# bm1397.net
KiCad netlist of a schematic drawn in EAGLE
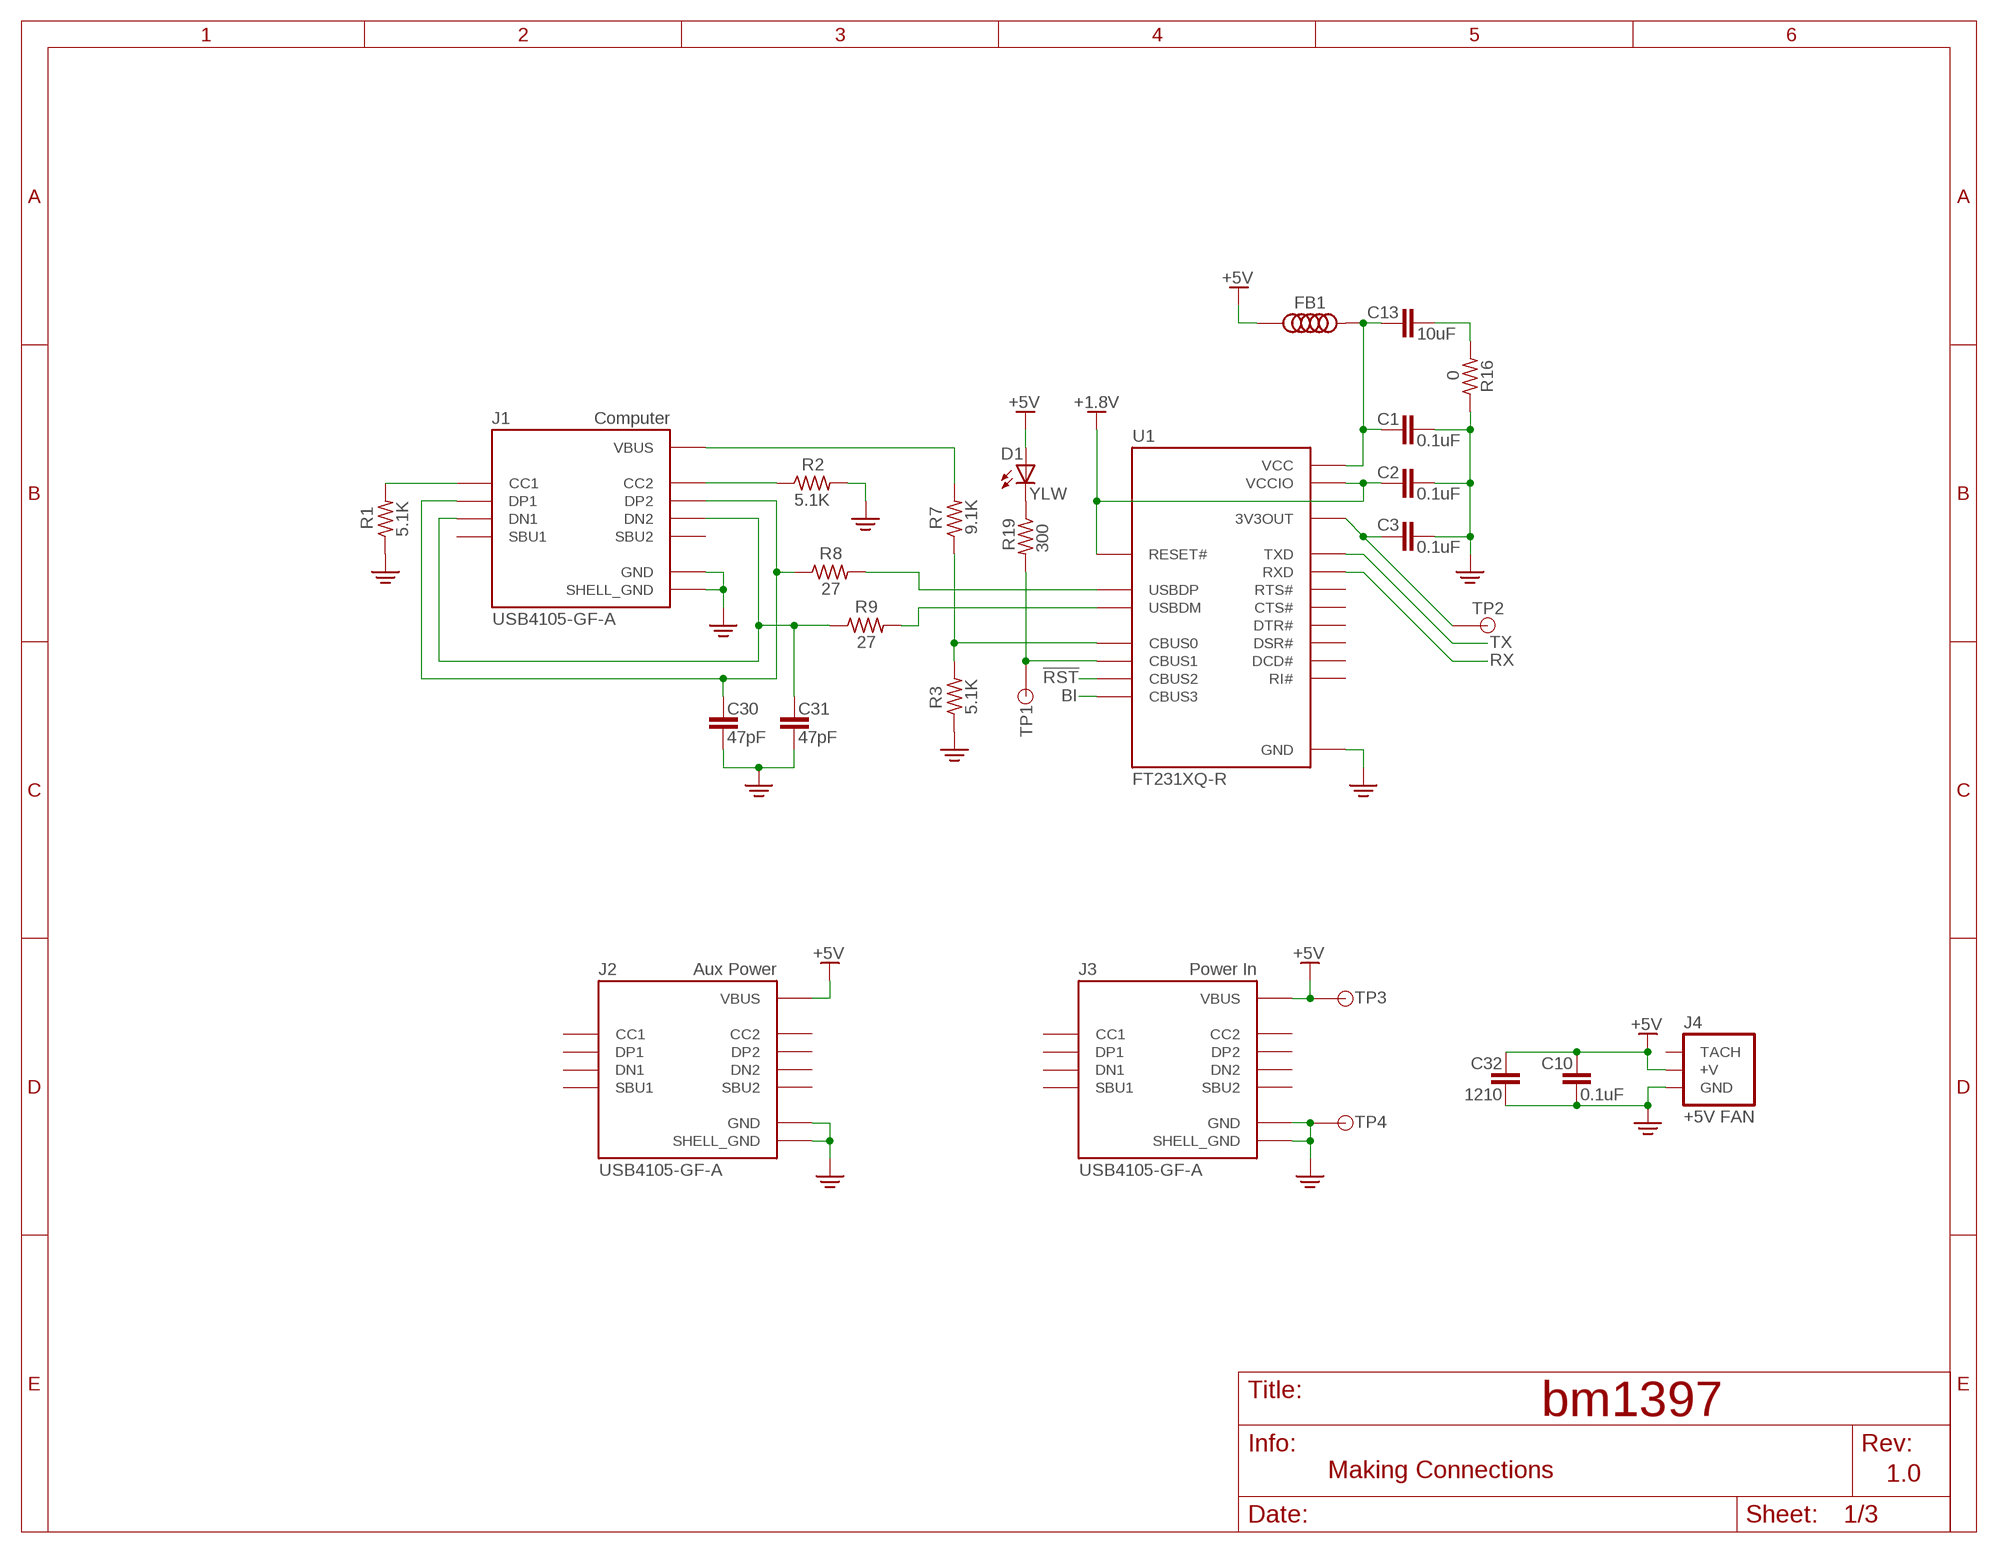
[diagram p0: schematic, sheet 1]
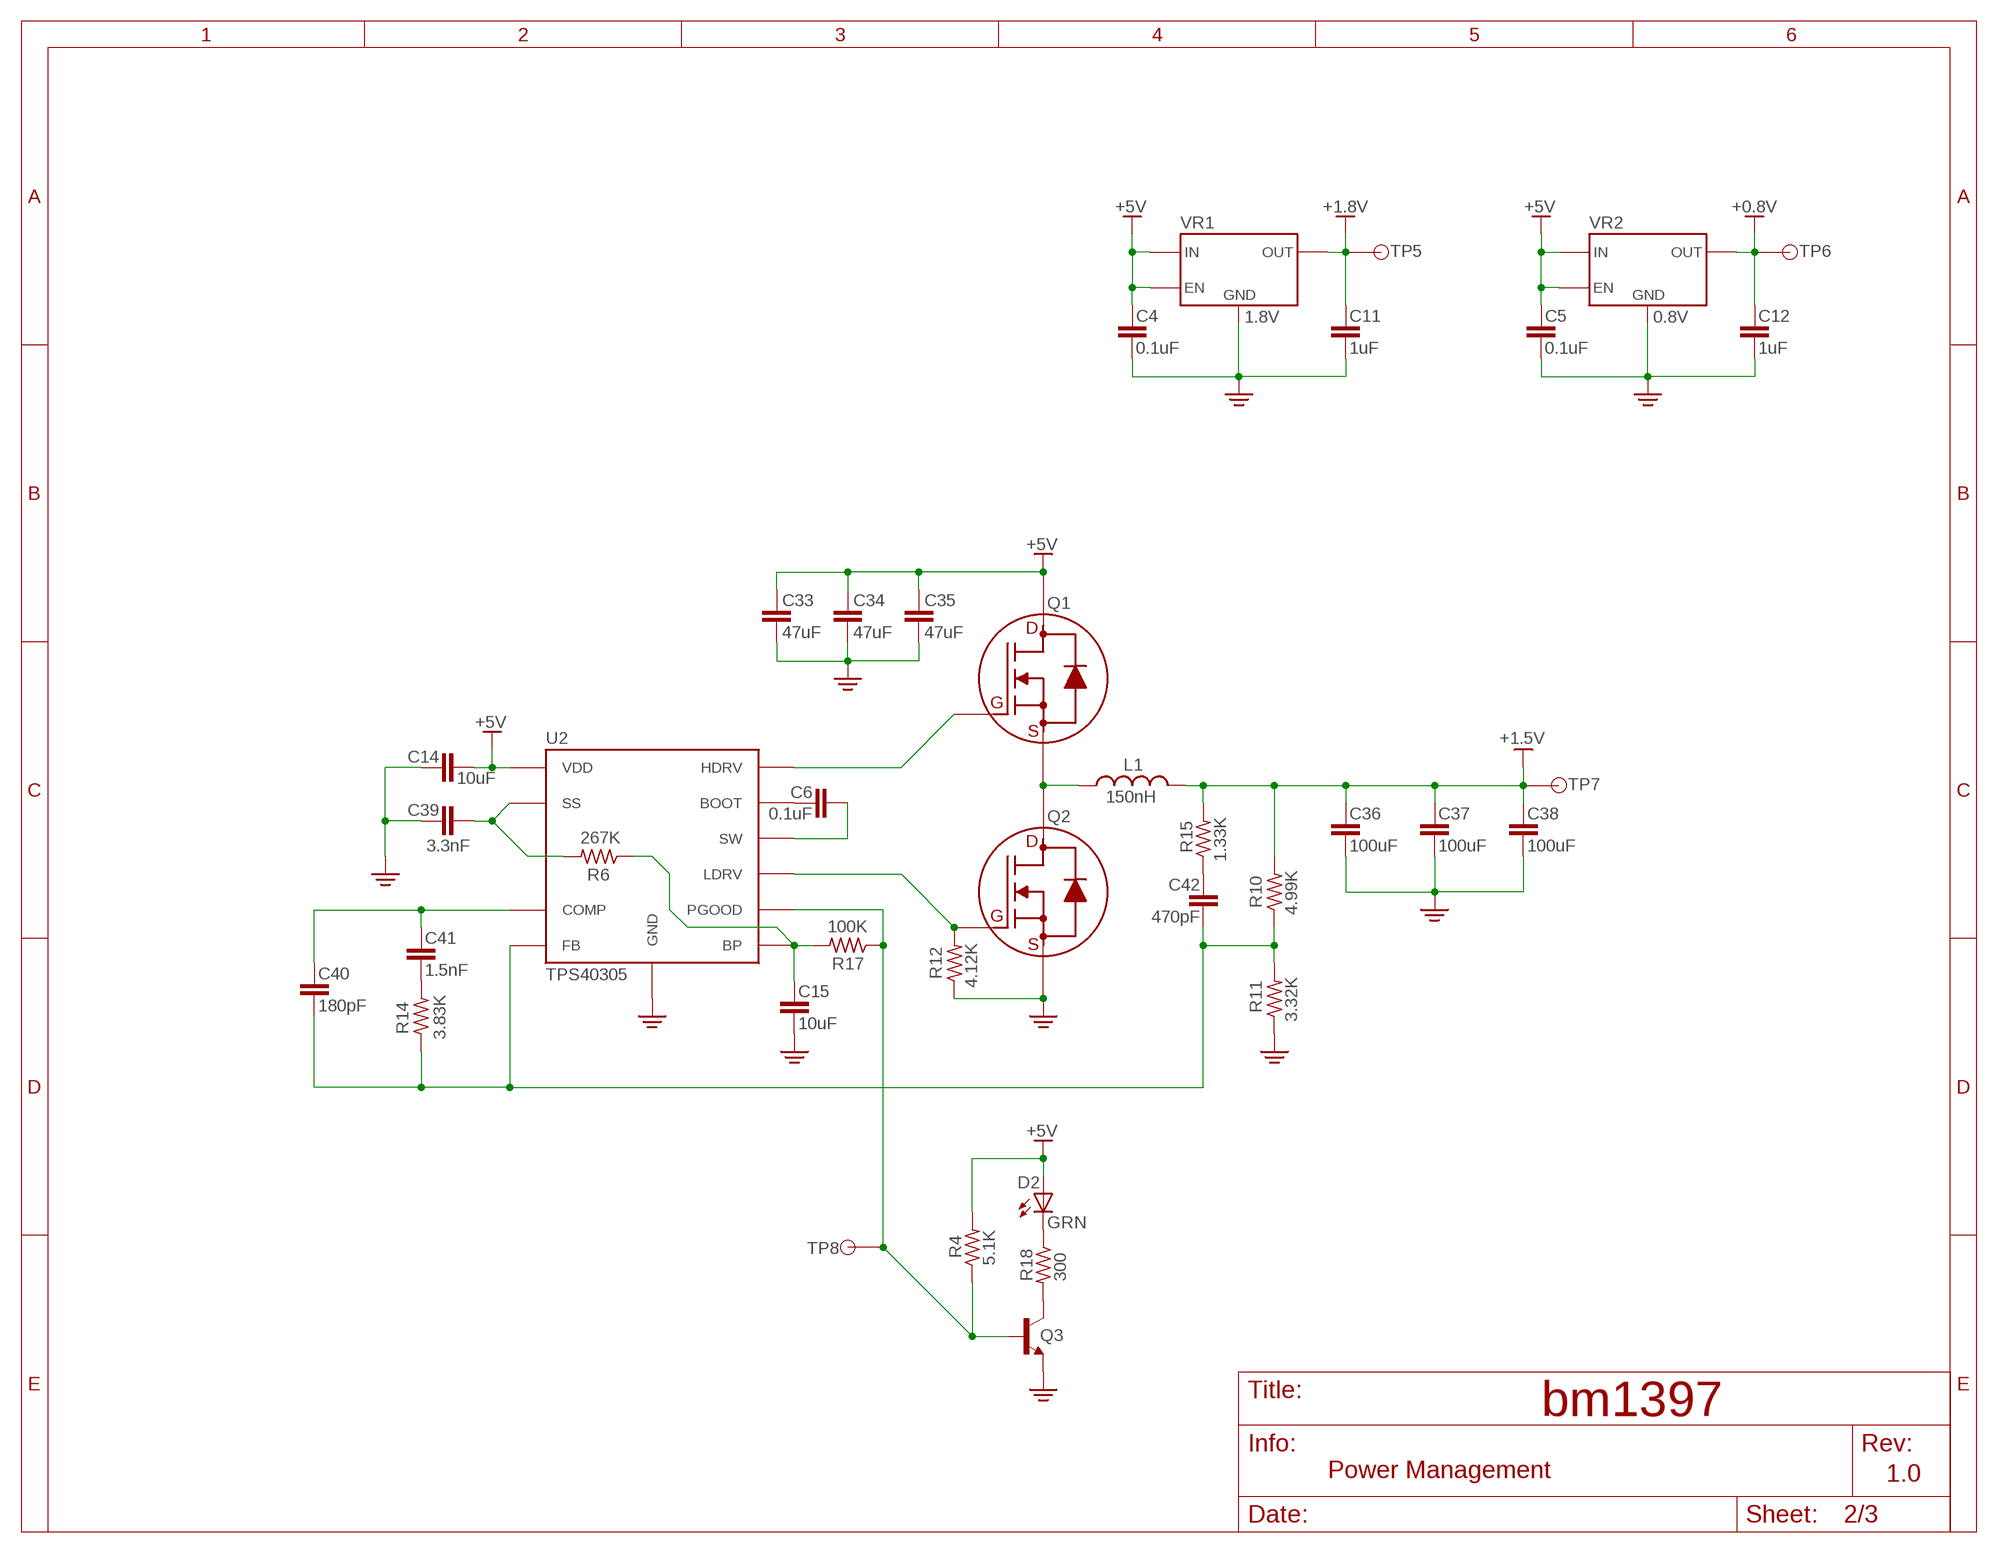
[diagram p1: schematic, sheet 2]
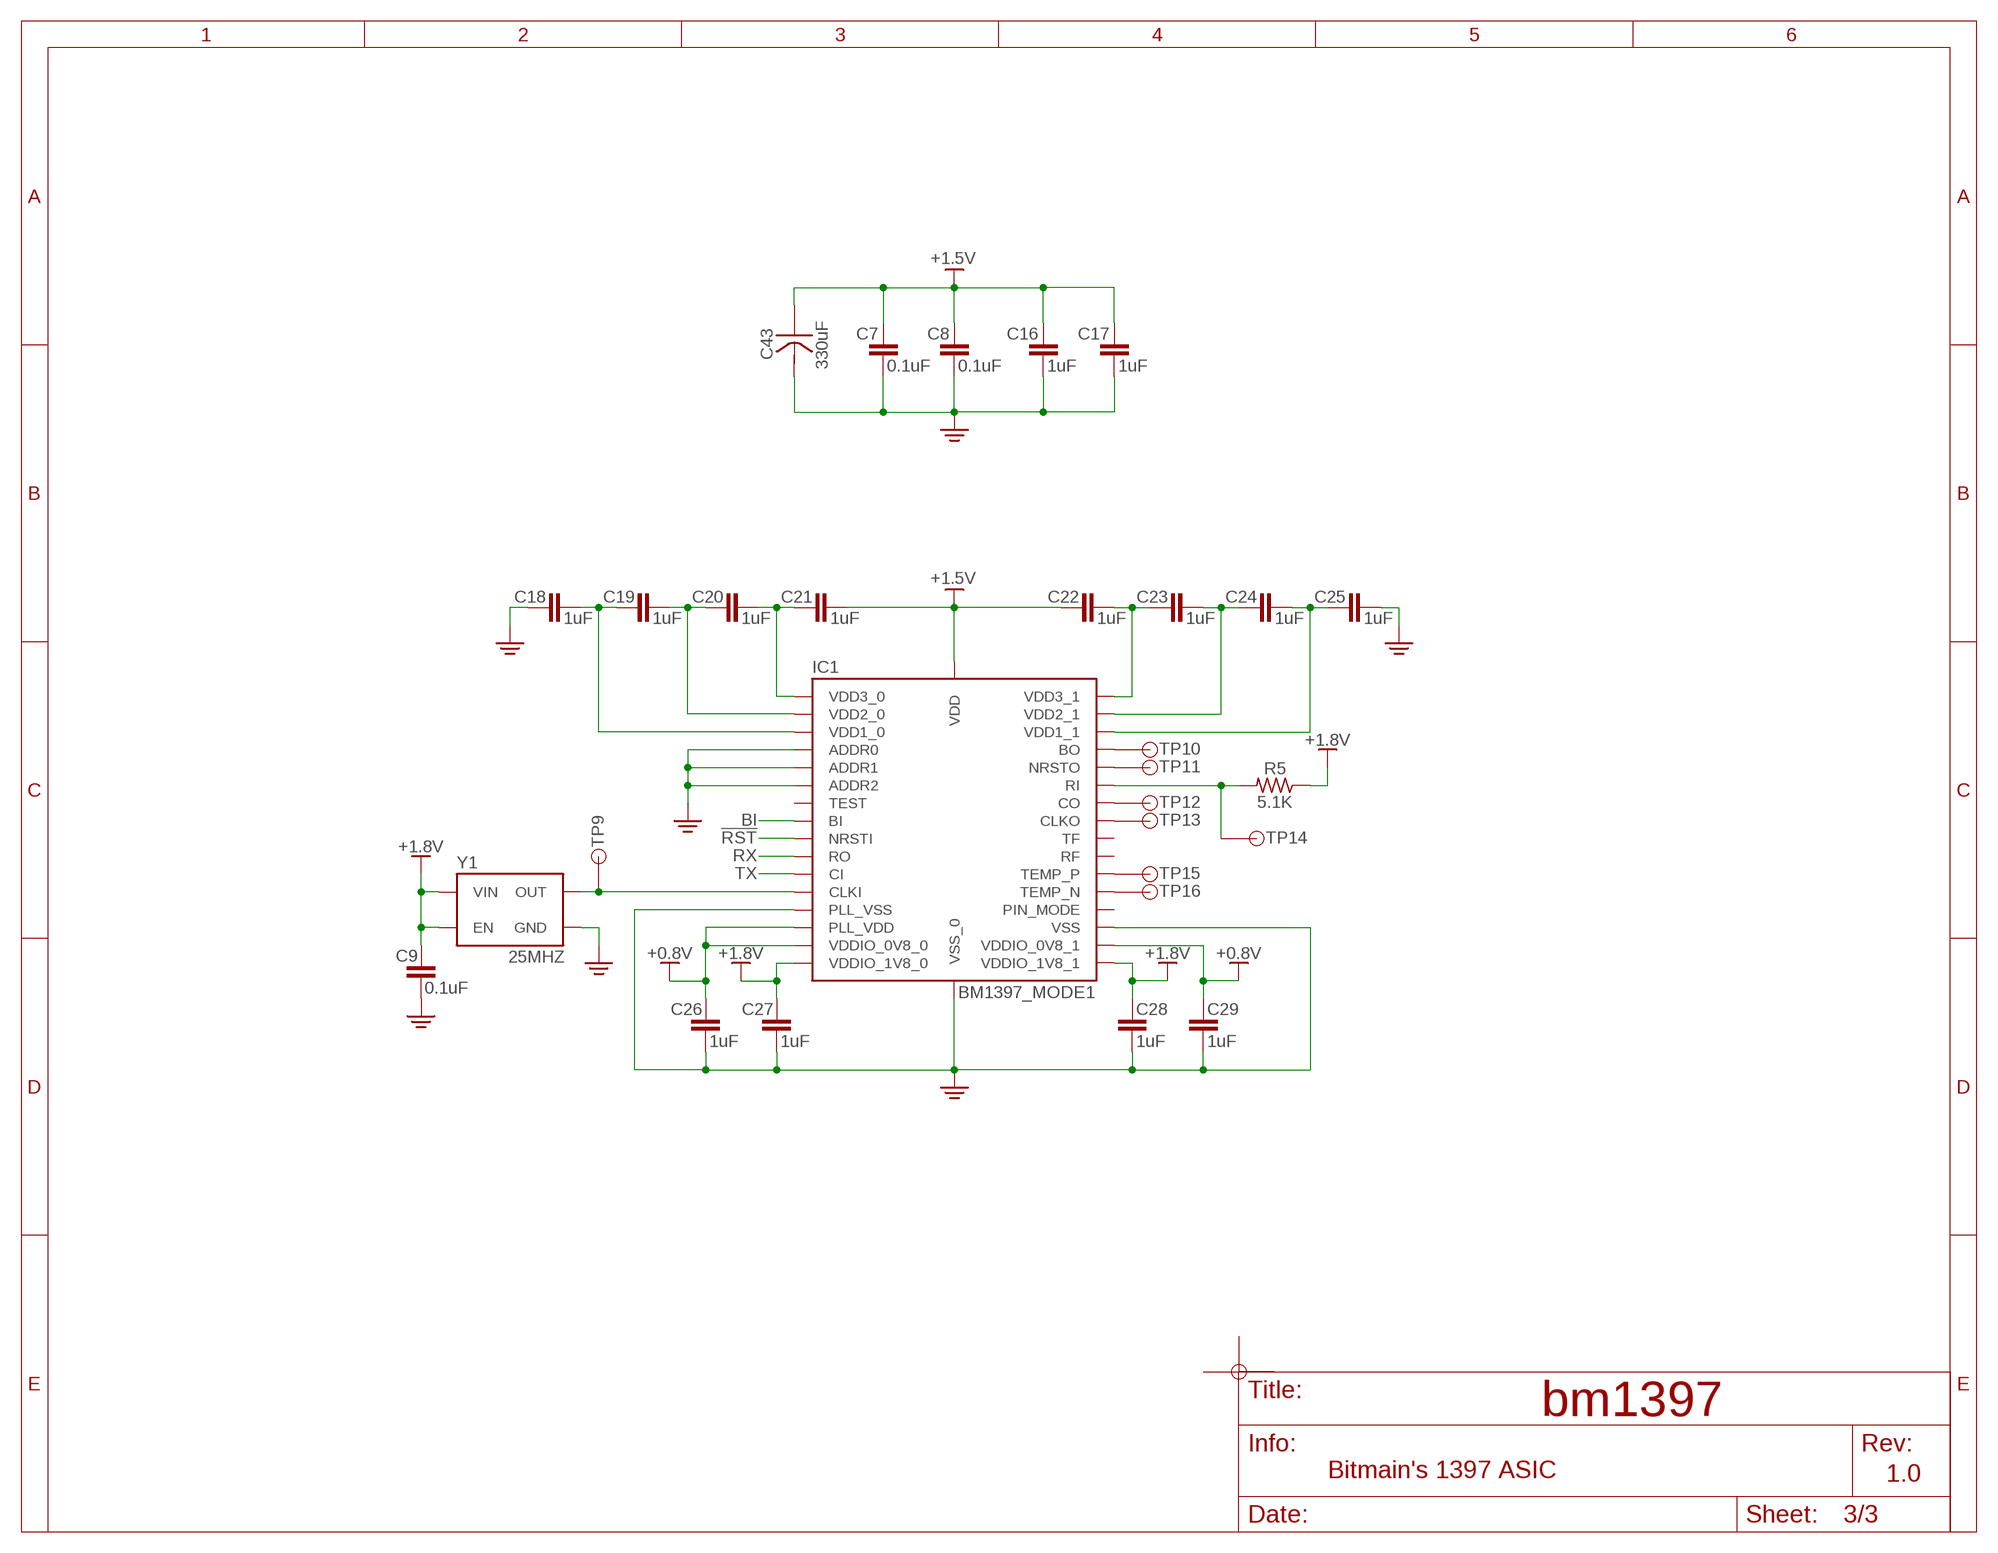
[diagram p2: schematic, sheet 3]

(export (version "E")
  (design (tool "Eeschema 10.0.6"))
  (components
    (comp (ref "BOTFIDUCIAL1")
      (value "TESTPOINT")
      (footprint "eagle-import:0.035")
      (libsource (lib "eagle-import") (part "TESTPOINT"))
    )
    (comp (ref "BOTFIDUCIAL2")
      (value "TESTPOINT")
      (footprint "eagle-import:0.035")
      (libsource (lib "eagle-import") (part "TESTPOINT"))
    )
    (comp (ref "BOTFIDUCIAL3")
      (value "TESTPOINT")
      (footprint "eagle-import:0.035")
      (libsource (lib "eagle-import") (part "TESTPOINT"))
    )
    (comp (ref "C7")
      (value "0.1uF")
      (footprint "eagle-import:C0402")
      (libsource (lib "eagle-import") (part "NPOL_CAPACITORC0402"))
    )
    (comp (ref "C8")
      (value "0.1uF")
      (footprint "eagle-import:C0402")
      (libsource (lib "eagle-import") (part "NPOL_CAPACITORC0402"))
    )
    (comp (ref "C9")
      (value "0.1uF")
      (footprint "eagle-import:C0402")
      (libsource (lib "eagle-import") (part "NPOL_CAPACITORC0402"))
    )
    (comp (ref "C16")
      (value "1uF")
      (footprint "eagle-import:C0603")
      (libsource (lib "eagle-import") (part "NPOL_CAPACITORC0603"))
    )
    (comp (ref "C17")
      (value "1uF")
      (footprint "eagle-import:C0603")
      (libsource (lib "eagle-import") (part "NPOL_CAPACITORC0603"))
    )
    (comp (ref "C18")
      (value "1uF")
      (footprint "eagle-import:C0603")
      (libsource (lib "eagle-import") (part "NPOL_CAPACITORC0603"))
    )
    (comp (ref "C19")
      (value "1uF")
      (footprint "eagle-import:C0603")
      (libsource (lib "eagle-import") (part "NPOL_CAPACITORC0603"))
    )
    (comp (ref "C20")
      (value "1uF")
      (footprint "eagle-import:C0603")
      (libsource (lib "eagle-import") (part "NPOL_CAPACITORC0603"))
    )
    (comp (ref "C21")
      (value "1uF")
      (footprint "eagle-import:C0603")
      (libsource (lib "eagle-import") (part "NPOL_CAPACITORC0603"))
    )
    (comp (ref "C22")
      (value "1uF")
      (footprint "eagle-import:C0603")
      (libsource (lib "eagle-import") (part "NPOL_CAPACITORC0603"))
    )
    (comp (ref "C23")
      (value "1uF")
      (footprint "eagle-import:C0603")
      (libsource (lib "eagle-import") (part "NPOL_CAPACITORC0603"))
    )
    (comp (ref "C24")
      (value "1uF")
      (footprint "eagle-import:C0603")
      (libsource (lib "eagle-import") (part "NPOL_CAPACITORC0603"))
    )
    (comp (ref "C25")
      (value "1uF")
      (footprint "eagle-import:C0603")
      (libsource (lib "eagle-import") (part "NPOL_CAPACITORC0603"))
    )
    (comp (ref "C26")
      (value "1uF")
      (footprint "eagle-import:C0603")
      (libsource (lib "eagle-import") (part "NPOL_CAPACITORC0603"))
    )
    (comp (ref "C27")
      (value "1uF")
      (footprint "eagle-import:C0603")
      (libsource (lib "eagle-import") (part "NPOL_CAPACITORC0603"))
    )
    (comp (ref "C28")
      (value "1uF")
      (footprint "eagle-import:C0603")
      (libsource (lib "eagle-import") (part "NPOL_CAPACITORC0603"))
    )
    (comp (ref "C29")
      (value "1uF")
      (footprint "eagle-import:C0603")
      (libsource (lib "eagle-import") (part "NPOL_CAPACITORC0603"))
    )
    (comp (ref "C43")
      (value "330uF")
      (footprint "eagle-import:TANT_3.5MMX2.8MM")
      (libsource (lib "eagle-import") (part "POL_CAPACITORTANT_3.5MMX2.8MM"))
    )
    (comp (ref "IC1")
      (value "BM1397_MODE1")
      (footprint "eagle-import:BM1397")
      (libsource (lib "eagle-import") (part "BM1397_MODE1"))
    )
    (comp (ref "R5")
      (value "5.1K")
      (footprint "eagle-import:R0402")
      (libsource (lib "eagle-import") (part "RESISTORR0402"))
    )
    (comp (ref "TOPFIDUCIAL1")
      (value "TESTPOINT")
      (footprint "eagle-import:0.035")
      (libsource (lib "eagle-import") (part "TESTPOINT"))
    )
    (comp (ref "TOPFIDUCIAL2")
      (value "TESTPOINT")
      (footprint "eagle-import:0.035")
      (libsource (lib "eagle-import") (part "TESTPOINT"))
    )
    (comp (ref "TOPFIDUCIAL3")
      (value "TESTPOINT")
      (footprint "eagle-import:0.035")
      (libsource (lib "eagle-import") (part "TESTPOINT"))
    )
    (comp (ref "TP9")
      (value "TESTPOINT")
      (footprint "eagle-import:0.035")
      (libsource (lib "eagle-import") (part "TESTPOINT"))
    )
    (comp (ref "TP10")
      (value "TESTPOINT")
      (footprint "eagle-import:0.035")
      (libsource (lib "eagle-import") (part "TESTPOINT"))
    )
    (comp (ref "TP11")
      (value "TESTPOINT")
      (footprint "eagle-import:0.035")
      (libsource (lib "eagle-import") (part "TESTPOINT"))
    )
    (comp (ref "TP12")
      (value "TESTPOINT")
      (footprint "eagle-import:0.035")
      (libsource (lib "eagle-import") (part "TESTPOINT"))
    )
    (comp (ref "TP13")
      (value "TESTPOINT")
      (footprint "eagle-import:0.035")
      (libsource (lib "eagle-import") (part "TESTPOINT"))
    )
    (comp (ref "TP14")
      (value "TESTPOINT")
      (footprint "eagle-import:0.035")
      (libsource (lib "eagle-import") (part "TESTPOINT"))
    )
    (comp (ref "TP15")
      (value "TESTPOINT")
      (footprint "eagle-import:0.035")
      (libsource (lib "eagle-import") (part "TESTPOINT"))
    )
    (comp (ref "TP16")
      (value "TESTPOINT")
      (footprint "eagle-import:0.035")
      (libsource (lib "eagle-import") (part "TESTPOINT"))
    )
    (comp (ref "Y1")
      (value "25MHZ")
      (footprint "eagle-import:JO32_3.20MMX2.50MM")
      (libsource (lib "eagle-import") (part "JO32_OSCILLATOR"))
    )
    (comp (ref "C1")
      (value "0.1uF")
      (footprint "eagle-import:C0402")
      (libsource (lib "eagle-import") (part "NPOL_CAPACITORC0402"))
    )
    (comp (ref "C2")
      (value "0.1uF")
      (footprint "eagle-import:C0402")
      (libsource (lib "eagle-import") (part "NPOL_CAPACITORC0402"))
    )
    (comp (ref "C3")
      (value "0.1uF")
      (footprint "eagle-import:C0402")
      (libsource (lib "eagle-import") (part "NPOL_CAPACITORC0402"))
    )
    (comp (ref "C10")
      (value "0.1uF")
      (footprint "eagle-import:C0402")
      (libsource (lib "eagle-import") (part "NPOL_CAPACITORC0402"))
    )
    (comp (ref "C13")
      (value "10uF")
      (footprint "eagle-import:C0805")
      (libsource (lib "eagle-import") (part "NPOL_CAPACITORC0805"))
    )
    (comp (ref "C30")
      (value "47pF")
      (footprint "eagle-import:C0402")
      (libsource (lib "eagle-import") (part "NPOL_CAPACITORC0402"))
    )
    (comp (ref "C31")
      (value "47pF")
      (footprint "eagle-import:C0402")
      (libsource (lib "eagle-import") (part "NPOL_CAPACITORC0402"))
    )
    (comp (ref "C32")
      (value "1210")
      (footprint "eagle-import:C1210")
      (libsource (lib "eagle-import") (part "NPOL_CAPACITORC1210"))
    )
    (comp (ref "D1")
      (value "YLW")
      (footprint "eagle-import:0805_SD_MNT")
      (libsource (lib "eagle-import") (part "LED"))
    )
    (comp (ref "FB1")
      (value "FERRITE_BEADF0402")
      (footprint "eagle-import:F0402")
      (libsource (lib "eagle-import") (part "FERRITE_BEADF0402"))
    )
    (comp (ref "J1")
      (value "USB4105-GF-A")
      (footprint "eagle-import:GCT_USB4105-GF-A")
      (fields (field (name "MF") "GCT"))
      (libsource (lib "eagle-import") (part "USB4105-GF-A"))
    )
    (comp (ref "J2")
      (value "USB4105-GF-A")
      (footprint "eagle-import:GCT_USB4105-GF-A")
      (fields (field (name "MF") "GCT"))
      (libsource (lib "eagle-import") (part "USB4105-GF-A"))
    )
    (comp (ref "J3")
      (value "USB4105-GF-A")
      (footprint "eagle-import:GCT_USB4105-GF-A")
      (fields (field (name "MF") "GCT"))
      (libsource (lib "eagle-import") (part "USB4105-GF-A"))
    )
    (comp (ref "J4")
      (value "+5V FAN")
      (footprint "eagle-import:3PIN_LOCK_HEADER")
      (libsource (lib "eagle-import") (part "3PIN_FAN3PIN_FAN"))
    )
    (comp (ref "R1")
      (value "5.1K")
      (footprint "eagle-import:R0402")
      (libsource (lib "eagle-import") (part "RESISTORR0402"))
    )
    (comp (ref "R2")
      (value "5.1K")
      (footprint "eagle-import:R0402")
      (libsource (lib "eagle-import") (part "RESISTORR0402"))
    )
    (comp (ref "R3")
      (value "5.1K")
      (footprint "eagle-import:R0402")
      (libsource (lib "eagle-import") (part "RESISTORR0402"))
    )
    (comp (ref "R7")
      (value "9.1K")
      (footprint "eagle-import:R0402")
      (libsource (lib "eagle-import") (part "RESISTORR0402"))
    )
    (comp (ref "R8")
      (value "27")
      (footprint "eagle-import:R0402")
      (libsource (lib "eagle-import") (part "RESISTORR0402"))
    )
    (comp (ref "R9")
      (value "27")
      (footprint "eagle-import:R0402")
      (libsource (lib "eagle-import") (part "RESISTORR0402"))
    )
    (comp (ref "R16")
      (value "0")
      (footprint "eagle-import:R0402")
      (libsource (lib "eagle-import") (part "RESISTORR0402"))
    )
    (comp (ref "R19")
      (value "300")
      (footprint "eagle-import:R0402")
      (libsource (lib "eagle-import") (part "RESISTORR0402"))
    )
    (comp (ref "TP1")
      (value "TESTPOINT")
      (footprint "eagle-import:0.035")
      (libsource (lib "eagle-import") (part "TESTPOINT"))
    )
    (comp (ref "TP2")
      (value "TESTPOINT")
      (footprint "eagle-import:0.035")
      (libsource (lib "eagle-import") (part "TESTPOINT"))
    )
    (comp (ref "TP3")
      (value "TESTPOINT")
      (footprint "eagle-import:0.035")
      (libsource (lib "eagle-import") (part "TESTPOINT"))
    )
    (comp (ref "TP4")
      (value "TESTPOINT")
      (footprint "eagle-import:0.035")
      (libsource (lib "eagle-import") (part "TESTPOINT"))
    )
    (comp (ref "U1")
      (value "FT231XQ-R")
      (footprint "eagle-import:QFN50P400X400X80-21N")
      (fields (field (name "MF") "FTDI, Future"))
      (libsource (lib "eagle-import") (part "FT231XQ-R"))
    )
    (comp (ref "C4")
      (value "0.1uF")
      (footprint "eagle-import:C0402")
      (libsource (lib "eagle-import") (part "NPOL_CAPACITORC0402"))
    )
    (comp (ref "C5")
      (value "0.1uF")
      (footprint "eagle-import:C0402")
      (libsource (lib "eagle-import") (part "NPOL_CAPACITORC0402"))
    )
    (comp (ref "C6")
      (value "0.1uF")
      (footprint "eagle-import:C0402")
      (libsource (lib "eagle-import") (part "NPOL_CAPACITORC0402"))
    )
    (comp (ref "C11")
      (value "1uF")
      (footprint "eagle-import:C0603")
      (libsource (lib "eagle-import") (part "NPOL_CAPACITORC0603"))
    )
    (comp (ref "C12")
      (value "1uF")
      (footprint "eagle-import:C0603")
      (libsource (lib "eagle-import") (part "NPOL_CAPACITORC0603"))
    )
    (comp (ref "C14")
      (value "10uF")
      (footprint "eagle-import:C0805")
      (libsource (lib "eagle-import") (part "NPOL_CAPACITORC0805"))
    )
    (comp (ref "C15")
      (value "10uF")
      (footprint "eagle-import:C0805")
      (libsource (lib "eagle-import") (part "NPOL_CAPACITORC0805"))
    )
    (comp (ref "C33")
      (value "47uF")
      (footprint "eagle-import:C1210")
      (libsource (lib "eagle-import") (part "NPOL_CAPACITORC1210"))
    )
    (comp (ref "C34")
      (value "47uF")
      (footprint "eagle-import:C1210")
      (libsource (lib "eagle-import") (part "NPOL_CAPACITORC1210"))
    )
    (comp (ref "C35")
      (value "47uF")
      (footprint "eagle-import:C1210")
      (libsource (lib "eagle-import") (part "NPOL_CAPACITORC1210"))
    )
    (comp (ref "C36")
      (value "100uF")
      (footprint "eagle-import:C1210")
      (libsource (lib "eagle-import") (part "NPOL_CAPACITORC1210"))
    )
    (comp (ref "C37")
      (value "100uF")
      (footprint "eagle-import:C1210")
      (libsource (lib "eagle-import") (part "NPOL_CAPACITORC1210"))
    )
    (comp (ref "C38")
      (value "100uF")
      (footprint "eagle-import:C1210")
      (libsource (lib "eagle-import") (part "NPOL_CAPACITORC1210"))
    )
    (comp (ref "C39")
      (value "3.3nF")
      (footprint "eagle-import:C0402")
      (libsource (lib "eagle-import") (part "NPOL_CAPACITORC0402"))
    )
    (comp (ref "C40")
      (value "180pF")
      (footprint "eagle-import:C0402")
      (libsource (lib "eagle-import") (part "NPOL_CAPACITORC0402"))
    )
    (comp (ref "C41")
      (value "1.5nF")
      (footprint "eagle-import:C0402")
      (libsource (lib "eagle-import") (part "NPOL_CAPACITORC0402"))
    )
    (comp (ref "C42")
      (value "470pF")
      (footprint "eagle-import:C0402")
      (libsource (lib "eagle-import") (part "NPOL_CAPACITORC0402"))
    )
    (comp (ref "D2")
      (value "GRN")
      (footprint "eagle-import:0805_SD_MNT")
      (libsource (lib "eagle-import") (part "LED"))
    )
    (comp (ref "L1")
      (value "150nH")
      (footprint "eagle-import:10.2MMX7.0MM")
      (libsource (lib "eagle-import") (part "SMD_INDUCTOR10.2MMX7.0MM"))
    )
    (comp (ref "Q1")
      (value "8-PowerTDFN")
      (footprint "eagle-import:CSD17311Q5")
      (fields
        (field (name "MANUFACTURER_PART_NUMBER") "CSD17311Q5")
        (field (name "MOUSER_PART_NUMBER") "595-CSD17311Q5")
      )
      (libsource (lib "eagle-import") (part "CSD17311Q5"))
    )
    (comp (ref "Q2")
      (value "8-PowerTDFN")
      (footprint "eagle-import:CSD17311Q5")
      (fields
        (field (name "MANUFACTURER_PART_NUMBER") "CSD17311Q5")
        (field (name "MOUSER_PART_NUMBER") "595-CSD17311Q5")
      )
      (libsource (lib "eagle-import") (part "CSD17311Q5"))
    )
    (comp (ref "Q3")
      (value "NPN")
      (footprint "eagle-import:SOT23")
      (libsource (lib "eagle-import") (part "NPN"))
    )
    (comp (ref "R4")
      (value "5.1K")
      (footprint "eagle-import:R0402")
      (libsource (lib "eagle-import") (part "RESISTORR0402"))
    )
    (comp (ref "R6")
      (value "267K")
      (footprint "eagle-import:R0402")
      (libsource (lib "eagle-import") (part "RESISTORR0402"))
    )
    (comp (ref "R10")
      (value "4.99K")
      (footprint "eagle-import:R0402")
      (libsource (lib "eagle-import") (part "RESISTORR0402"))
    )
    (comp (ref "R11")
      (value "3.32K")
      (footprint "eagle-import:R0402")
      (libsource (lib "eagle-import") (part "RESISTORR0402"))
    )
    (comp (ref "R12")
      (value "4.12K")
      (footprint "eagle-import:R0402")
      (libsource (lib "eagle-import") (part "RESISTORR0402"))
    )
    (comp (ref "R14")
      (value "3.83K")
      (footprint "eagle-import:R0402")
      (libsource (lib "eagle-import") (part "RESISTORR0402"))
    )
    (comp (ref "R15")
      (value "1.33K")
      (footprint "eagle-import:R0402")
      (libsource (lib "eagle-import") (part "RESISTORR0402"))
    )
    (comp (ref "R17")
      (value "100K")
      (footprint "eagle-import:R0402")
      (libsource (lib "eagle-import") (part "RESISTORR0402"))
    )
    (comp (ref "R18")
      (value "300")
      (footprint "eagle-import:R0402")
      (libsource (lib "eagle-import") (part "RESISTORR0402"))
    )
    (comp (ref "TP5")
      (value "TESTPOINT")
      (footprint "eagle-import:0.035")
      (libsource (lib "eagle-import") (part "TESTPOINT"))
    )
    (comp (ref "TP6")
      (value "TESTPOINT")
      (footprint "eagle-import:0.035")
      (libsource (lib "eagle-import") (part "TESTPOINT"))
    )
    (comp (ref "TP7")
      (value "TESTPOINT")
      (footprint "eagle-import:0.035")
      (libsource (lib "eagle-import") (part "TESTPOINT"))
    )
    (comp (ref "TP8")
      (value "TESTPOINT")
      (footprint "eagle-import:0.035")
      (libsource (lib "eagle-import") (part "TESTPOINT"))
    )
    (comp (ref "U2")
      (value "TPS40305")
      (footprint "eagle-import:TPS40305")
      (fields
        (field (name "MANUFACTURER_PART_NUMBER") "TPS40305DRCT")
        (field (name "MOUSER_PART_NUMBER") "595-TPS40305DRCT")
      )
      (libsource (lib "eagle-import") (part "TPS40305"))
    )
    (comp (ref "VR1")
      (value "1.8V")
      (footprint "eagle-import:TSOP-5")
      (libsource (lib "eagle-import") (part "REGULATOR-ENTSOP-5"))
    )
    (comp (ref "VR2")
      (value "0.8V")
      (footprint "eagle-import:TSOP-5")
      (libsource (lib "eagle-import") (part "REGULATOR-ENTSOP-5"))
    )
  )
  (nets
    (net (code "1") (name "+0V8") (class "Default")
      (node (ref "C12") (pin "1") (pinfunction "1_1") (pintype "passive"))
      (node (ref "C26") (pin "1") (pinfunction "1_1") (pintype "passive"))
      (node (ref "C29") (pin "1") (pinfunction "1_1") (pintype "passive"))
      (node (ref "IC1") (pin "14") (pinfunction "PLL_VDD_14") (pintype "power_in"))
      (node (ref "IC1") (pin "15") (pinfunction "VDDIO_0V8_0_15") (pintype "power_in"))
      (node (ref "IC1") (pin "18") (pinfunction "VDDIO_0V8_1_18") (pintype "power_in"))
      (node (ref "TP6") (pin "TP") (pinfunction "TP_TP") (pintype "passive"))
      (node (ref "VR2") (pin "5") (pinfunction "OUT_5") (pintype "power_in"))
    )
    (net (code "2") (name "+1V5") (class "Default")
      (node (ref "C16") (pin "2") (pinfunction "2_2") (pintype "passive"))
      (node (ref "C17") (pin "2") (pinfunction "2_2") (pintype "passive"))
      (node (ref "C21") (pin "2") (pinfunction "2_2") (pintype "passive"))
      (node (ref "C22") (pin "2") (pinfunction "2_2") (pintype "passive"))
      (node (ref "C36") (pin "1") (pinfunction "1_1") (pintype "passive"))
      (node (ref "C37") (pin "1") (pinfunction "1_1") (pintype "passive"))
      (node (ref "C38") (pin "1") (pinfunction "1_1") (pintype "passive"))
      (node (ref "C43") (pin "A") (pinfunction "+_A") (pintype "passive"))
      (node (ref "C7") (pin "2") (pinfunction "2_2") (pintype "passive"))
      (node (ref "C8") (pin "2") (pinfunction "2_2") (pintype "passive"))
      (node (ref "IC1") (pin "33") (pinfunction "VDD_33") (pintype "power_in"))
      (node (ref "L1") (pin "2") (pinfunction "2_2") (pintype "passive"))
      (node (ref "R10") (pin "2") (pinfunction "2_2") (pintype "passive"))
      (node (ref "R15") (pin "2") (pinfunction "2_2") (pintype "passive"))
      (node (ref "TP7") (pin "TP") (pinfunction "TP_TP") (pintype "passive"))
    )
    (net (code "3") (name "+1V8") (class "Default")
      (node (ref "C11") (pin "1") (pinfunction "1_1") (pintype "passive"))
      (node (ref "C2") (pin "1") (pinfunction "1_1") (pintype "passive"))
      (node (ref "C27") (pin "1") (pinfunction "1_1") (pintype "passive"))
      (node (ref "C28") (pin "1") (pinfunction "1_1") (pintype "passive"))
      (node (ref "C9") (pin "2") (pinfunction "2_2") (pintype "passive"))
      (node (ref "IC1") (pin "16") (pinfunction "VDDIO_1V8_0_16") (pintype "power_in"))
      (node (ref "IC1") (pin "17") (pinfunction "VDDIO_1V8_1_17") (pintype "power_in"))
      (node (ref "R5") (pin "1") (pinfunction "1_1") (pintype "passive"))
      (node (ref "TP5") (pin "TP") (pinfunction "TP_TP") (pintype "passive"))
      (node (ref "U1") (pin "11") (pinfunction "RESET#_11") (pintype "input"))
      (node (ref "U1") (pin "20") (pinfunction "VCCIO_20") (pintype "power_in"))
      (node (ref "VR1") (pin "5") (pinfunction "OUT_5") (pintype "power_in"))
      (node (ref "Y1") (pin "1") (pinfunction "EN_1") (pintype "input"))
      (node (ref "Y1") (pin "4") (pinfunction "VIN_4") (pintype "power_in"))
    )
    (net (code "4") (name "+5V") (class "Default")
      (node (ref "C10") (pin "2") (pinfunction "2_2") (pintype "passive"))
      (node (ref "C14") (pin "1") (pinfunction "1_1") (pintype "passive"))
      (node (ref "C32") (pin "1") (pinfunction "1_1") (pintype "passive"))
      (node (ref "C33") (pin "1") (pinfunction "1_1") (pintype "passive"))
      (node (ref "C34") (pin "1") (pinfunction "1_1") (pintype "passive"))
      (node (ref "C35") (pin "1") (pinfunction "1_1") (pintype "passive"))
      (node (ref "C4") (pin "1") (pinfunction "1_1") (pintype "passive"))
      (node (ref "C5") (pin "1") (pinfunction "1_1") (pintype "passive"))
      (node (ref "D1") (pin "A") (pinfunction "A_A") (pintype "passive"))
      (node (ref "D2") (pin "A") (pinfunction "A_A") (pintype "passive"))
      (node (ref "FB1") (pin "1") (pinfunction "1_1") (pintype "passive"))
      (node (ref "J2") (pin "A4_B9") (pinfunction "VBUS_A4_B9") (pintype "power_in"))
      (node (ref "J2") (pin "B4_A9") (pinfunction "VBUS_B4_A9") (pintype "power_in"))
      (node (ref "J3") (pin "A4_B9") (pinfunction "VBUS_A4_B9") (pintype "power_in"))
      (node (ref "J3") (pin "B4_A9") (pinfunction "VBUS_B4_A9") (pintype "power_in"))
      (node (ref "J4") (pin "2") (pinfunction "+V_2") (pintype "passive"))
      (node (ref "Q1") (pin "5") (pinfunction "D_5") (pintype "passive"))
      (node (ref "Q1") (pin "6") (pinfunction "D_6") (pintype "passive"))
      (node (ref "Q1") (pin "7") (pinfunction "D_7") (pintype "passive"))
      (node (ref "Q1") (pin "8") (pinfunction "D_8") (pintype "passive"))
      (node (ref "Q1") (pin "9") (pinfunction "D_9") (pintype "passive"))
      (node (ref "R4") (pin "2") (pinfunction "2_2") (pintype "passive"))
      (node (ref "TP3") (pin "TP") (pinfunction "TP_TP") (pintype "passive"))
      (node (ref "U2") (pin "1") (pinfunction "VDD_1") (pintype "bidirectional"))
      (node (ref "VR1") (pin "1") (pinfunction "IN_1") (pintype "power_in"))
      (node (ref "VR1") (pin "3") (pinfunction "EN_3") (pintype "input"))
      (node (ref "VR2") (pin "1") (pinfunction "IN_1") (pintype "power_in"))
      (node (ref "VR2") (pin "3") (pinfunction "EN_3") (pintype "input"))
    )
    (net (code "5") (name "BI") (class "Default")
      (node (ref "IC1") (pin "8") (pinfunction "BI_8") (pintype "input"))
      (node (ref "U1") (pin "16") (pinfunction "CBUS3_16") (pintype "bidirectional"))
    )
    (net (code "6") (name "GND") (class "Default")
      (node (ref "C1") (pin "2") (pinfunction "2_2") (pintype "passive"))
      (node (ref "C10") (pin "1") (pinfunction "1_1") (pintype "passive"))
      (node (ref "C11") (pin "2") (pinfunction "2_2") (pintype "passive"))
      (node (ref "C12") (pin "2") (pinfunction "2_2") (pintype "passive"))
      (node (ref "C14") (pin "2") (pinfunction "2_2") (pintype "passive"))
      (node (ref "C15") (pin "2") (pinfunction "2_2") (pintype "passive"))
      (node (ref "C16") (pin "1") (pinfunction "1_1") (pintype "passive"))
      (node (ref "C17") (pin "1") (pinfunction "1_1") (pintype "passive"))
      (node (ref "C18") (pin "1") (pinfunction "1_1") (pintype "passive"))
      (node (ref "C2") (pin "2") (pinfunction "2_2") (pintype "passive"))
      (node (ref "C25") (pin "1") (pinfunction "1_1") (pintype "passive"))
      (node (ref "C26") (pin "2") (pinfunction "2_2") (pintype "passive"))
      (node (ref "C27") (pin "2") (pinfunction "2_2") (pintype "passive"))
      (node (ref "C28") (pin "2") (pinfunction "2_2") (pintype "passive"))
      (node (ref "C29") (pin "2") (pinfunction "2_2") (pintype "passive"))
      (node (ref "C3") (pin "2") (pinfunction "2_2") (pintype "passive"))
      (node (ref "C30") (pin "1") (pinfunction "1_1") (pintype "passive"))
      (node (ref "C31") (pin "1") (pinfunction "1_1") (pintype "passive"))
      (node (ref "C32") (pin "2") (pinfunction "2_2") (pintype "passive"))
      (node (ref "C33") (pin "2") (pinfunction "2_2") (pintype "passive"))
      (node (ref "C34") (pin "2") (pinfunction "2_2") (pintype "passive"))
      (node (ref "C35") (pin "2") (pinfunction "2_2") (pintype "passive"))
      (node (ref "C36") (pin "2") (pinfunction "2_2") (pintype "passive"))
      (node (ref "C37") (pin "2") (pinfunction "2_2") (pintype "passive"))
      (node (ref "C38") (pin "2") (pinfunction "2_2") (pintype "passive"))
      (node (ref "C39") (pin "2") (pinfunction "2_2") (pintype "passive"))
      (node (ref "C4") (pin "2") (pinfunction "2_2") (pintype "passive"))
      (node (ref "C43") (pin "C") (pinfunction "-_C") (pintype "passive"))
      (node (ref "C5") (pin "2") (pinfunction "2_2") (pintype "passive"))
      (node (ref "C7") (pin "1") (pinfunction "1_1") (pintype "passive"))
      (node (ref "C8") (pin "1") (pinfunction "1_1") (pintype "passive"))
      (node (ref "C9") (pin "1") (pinfunction "1_1") (pintype "passive"))
      (node (ref "IC1") (pin "13") (pinfunction "PLL_VSS_13") (pintype "power_in"))
      (node (ref "IC1") (pin "19") (pinfunction "VSS_19") (pintype "power_in"))
      (node (ref "IC1") (pin "34") (pinfunction "VSS_0_34") (pintype "power_in"))
      (node (ref "IC1") (pin "4") (pinfunction "ADDR0_4") (pintype "input"))
      (node (ref "IC1") (pin "5") (pinfunction "ADDR1_5") (pintype "input"))
      (node (ref "IC1") (pin "6") (pinfunction "ADDR2_6") (pintype "input"))
      (node (ref "J1") (pin "A1_B12") (pinfunction "GND_A1_B12") (pintype "power_in"))
      (node (ref "J1") (pin "B1_A12") (pinfunction "GND_B1_A12") (pintype "power_in"))
      (node (ref "J1") (pin "S1") (pinfunction "SHELL_GND_S1") (pintype "power_in"))
      (node (ref "J1") (pin "S2") (pinfunction "SHELL_GND_S2") (pintype "power_in"))
      (node (ref "J1") (pin "S3") (pinfunction "SHELL_GND_S3") (pintype "power_in"))
      (node (ref "J1") (pin "S4") (pinfunction "SHELL_GND_S4") (pintype "power_in"))
      (node (ref "J2") (pin "A1_B12") (pinfunction "GND_A1_B12") (pintype "power_in"))
      (node (ref "J2") (pin "B1_A12") (pinfunction "GND_B1_A12") (pintype "power_in"))
      (node (ref "J2") (pin "S1") (pinfunction "SHELL_GND_S1") (pintype "power_in"))
      (node (ref "J2") (pin "S2") (pinfunction "SHELL_GND_S2") (pintype "power_in"))
      (node (ref "J2") (pin "S3") (pinfunction "SHELL_GND_S3") (pintype "power_in"))
      (node (ref "J2") (pin "S4") (pinfunction "SHELL_GND_S4") (pintype "power_in"))
      (node (ref "J3") (pin "A1_B12") (pinfunction "GND_A1_B12") (pintype "power_in"))
      (node (ref "J3") (pin "B1_A12") (pinfunction "GND_B1_A12") (pintype "power_in"))
      (node (ref "J3") (pin "S1") (pinfunction "SHELL_GND_S1") (pintype "power_in"))
      (node (ref "J3") (pin "S2") (pinfunction "SHELL_GND_S2") (pintype "power_in"))
      (node (ref "J3") (pin "S3") (pinfunction "SHELL_GND_S3") (pintype "power_in"))
      (node (ref "J3") (pin "S4") (pinfunction "SHELL_GND_S4") (pintype "power_in"))
      (node (ref "J4") (pin "1") (pinfunction "GND_1") (pintype "passive"))
      (node (ref "Q2") (pin "1") (pinfunction "S_1") (pintype "passive"))
      (node (ref "Q2") (pin "2") (pinfunction "S_2") (pintype "passive"))
      (node (ref "Q2") (pin "3") (pinfunction "S_3") (pintype "passive"))
      (node (ref "Q3") (pin "2") (pinfunction "E_2") (pintype "passive"))
      (node (ref "R1") (pin "1") (pinfunction "1_1") (pintype "passive"))
      (node (ref "R11") (pin "1") (pinfunction "1_1") (pintype "passive"))
      (node (ref "R12") (pin "1") (pinfunction "1_1") (pintype "passive"))
      (node (ref "R16") (pin "1") (pinfunction "1_1") (pintype "passive"))
      (node (ref "R2") (pin "2") (pinfunction "2_2") (pintype "passive"))
      (node (ref "R3") (pin "1") (pinfunction "1_1") (pintype "passive"))
      (node (ref "TP4") (pin "TP") (pinfunction "TP_TP") (pintype "passive"))
      (node (ref "U1") (pin "13") (pinfunction "GND_13") (pintype "power_in"))
      (node (ref "U1") (pin "21") (pinfunction "GND_21") (pintype "power_in"))
      (node (ref "U1") (pin "3") (pinfunction "GND_3") (pintype "power_in"))
      (node (ref "U2") (pin "11") (pinfunction "GND_11") (pintype "bidirectional"))
      (node (ref "U2") (pin "12") (pinfunction "GND_12") (pintype "bidirectional"))
      (node (ref "U2") (pin "13") (pinfunction "GND_13") (pintype "bidirectional"))
      (node (ref "U2") (pin "14") (pinfunction "GND_14") (pintype "bidirectional"))
      (node (ref "U2") (pin "15") (pinfunction "GND_15") (pintype "bidirectional"))
      (node (ref "VR1") (pin "2") (pinfunction "GND_2") (pintype "power_in"))
      (node (ref "VR2") (pin "2") (pinfunction "GND_2") (pintype "power_in"))
      (node (ref "Y1") (pin "2") (pinfunction "GND_2") (pintype "power_in"))
    )
    (net (code "7") (name "Net-(BOTFIDUCIAL2-PadTP)") (class "Default")
      (node (ref "BOTFIDUCIAL2") (pin "TP") (pinfunction "TP_TP") (pintype "passive"))
      (node (ref "TOPFIDUCIAL1") (pin "TP") (pinfunction "TP_TP") (pintype "passive"))
    )
    (net (code "8") (name "Net-(BOTFIDUCIAL3-PadTP)") (class "Default")
      (node (ref "BOTFIDUCIAL3") (pin "TP") (pinfunction "TP_TP") (pintype "passive"))
      (node (ref "TOPFIDUCIAL3") (pin "TP") (pinfunction "TP_TP") (pintype "passive"))
    )
    (net (code "9") (name "Net-(C13-Pad2)") (class "Default")
      (node (ref "C13") (pin "2") (pinfunction "2_2") (pintype "passive"))
      (node (ref "R16") (pin "2") (pinfunction "2_2") (pintype "passive"))
    )
    (net (code "10") (name "Net-(C41-Pad2)") (class "Default")
      (node (ref "C41") (pin "2") (pinfunction "2_2") (pintype "passive"))
      (node (ref "R14") (pin "2") (pinfunction "2_2") (pintype "passive"))
    )
    (net (code "11") (name "Net-(C42-Pad1)") (class "Default")
      (node (ref "C42") (pin "1") (pinfunction "1_1") (pintype "passive"))
      (node (ref "R15") (pin "1") (pinfunction "1_1") (pintype "passive"))
    )
    (net (code "12") (name "Net-(D1-PadC)") (class "Default")
      (node (ref "D1") (pin "C") (pinfunction "C_C") (pintype "passive"))
      (node (ref "R19") (pin "1") (pinfunction "1_1") (pintype "passive"))
    )
    (net (code "13") (name "Net-(D2-PadC)") (class "Default")
      (node (ref "D2") (pin "C") (pinfunction "C_C") (pintype "passive"))
      (node (ref "R18") (pin "1") (pinfunction "1_1") (pintype "passive"))
    )
    (net (code "14") (name "Net-(IC1-BO)") (class "Default")
      (node (ref "IC1") (pin "29") (pinfunction "BO_29") (pintype "output"))
      (node (ref "TP10") (pin "TP") (pinfunction "TP_TP") (pintype "passive"))
    )
    (net (code "15") (name "Net-(IC1-CLKI)") (class "Default")
      (node (ref "IC1") (pin "12") (pinfunction "CLKI_12") (pintype "input"))
      (node (ref "TP9") (pin "TP") (pinfunction "TP_TP") (pintype "passive"))
      (node (ref "Y1") (pin "3") (pinfunction "OUT_3") (pintype "output"))
    )
    (net (code "16") (name "Net-(IC1-CLKO)") (class "Default")
      (node (ref "IC1") (pin "25") (pinfunction "CLKO_25") (pintype "output"))
      (node (ref "TP13") (pin "TP") (pinfunction "TP_TP") (pintype "passive"))
    )
    (net (code "17") (name "Net-(IC1-CO)") (class "Default")
      (node (ref "IC1") (pin "26") (pinfunction "CO_26") (pintype "output"))
      (node (ref "TP12") (pin "TP") (pinfunction "TP_TP") (pintype "passive"))
    )
    (net (code "18") (name "Net-(IC1-NRSTO)") (class "Default")
      (node (ref "IC1") (pin "28") (pinfunction "NRSTO_28") (pintype "output"))
      (node (ref "TP11") (pin "TP") (pinfunction "TP_TP") (pintype "passive"))
    )
    (net (code "19") (name "Net-(IC1-RI)") (class "Default")
      (node (ref "IC1") (pin "27") (pinfunction "RI_27") (pintype "input"))
      (node (ref "R5") (pin "2") (pinfunction "2_2") (pintype "passive"))
      (node (ref "TP14") (pin "TP") (pinfunction "TP_TP") (pintype "passive"))
    )
    (net (code "20") (name "Net-(IC1-TEMP_N)") (class "Default")
      (node (ref "IC1") (pin "21") (pinfunction "TEMP_N_21") (pintype "passive"))
      (node (ref "TP16") (pin "TP") (pinfunction "TP_TP") (pintype "passive"))
    )
    (net (code "21") (name "Net-(IC1-TEMP_P)") (class "Default")
      (node (ref "IC1") (pin "22") (pinfunction "TEMP_P_22") (pintype "passive"))
      (node (ref "TP15") (pin "TP") (pinfunction "TP_TP") (pintype "passive"))
    )
    (net (code "22") (name "Net-(IC1-VDD1_0)") (class "Default")
      (node (ref "C18") (pin "2") (pinfunction "2_2") (pintype "passive"))
      (node (ref "C19") (pin "1") (pinfunction "1_1") (pintype "passive"))
      (node (ref "IC1") (pin "3") (pinfunction "VDD1_0_3") (pintype "power_in"))
    )
    (net (code "23") (name "Net-(IC1-VDD1_1)") (class "Default")
      (node (ref "C24") (pin "1") (pinfunction "1_1") (pintype "passive"))
      (node (ref "C25") (pin "2") (pinfunction "2_2") (pintype "passive"))
      (node (ref "IC1") (pin "30") (pinfunction "VDD1_1_30") (pintype "power_in"))
    )
    (net (code "24") (name "Net-(IC1-VDD2_0)") (class "Default")
      (node (ref "C19") (pin "2") (pinfunction "2_2") (pintype "passive"))
      (node (ref "C20") (pin "1") (pinfunction "1_1") (pintype "passive"))
      (node (ref "IC1") (pin "2") (pinfunction "VDD2_0_2") (pintype "power_in"))
    )
    (net (code "25") (name "Net-(IC1-VDD2_1)") (class "Default")
      (node (ref "C23") (pin "1") (pinfunction "1_1") (pintype "passive"))
      (node (ref "C24") (pin "2") (pinfunction "2_2") (pintype "passive"))
      (node (ref "IC1") (pin "31") (pinfunction "VDD2_1_31") (pintype "power_in"))
    )
    (net (code "26") (name "Net-(IC1-VDD3_0)") (class "Default")
      (node (ref "C20") (pin "2") (pinfunction "2_2") (pintype "passive"))
      (node (ref "C21") (pin "1") (pinfunction "1_1") (pintype "passive"))
      (node (ref "IC1") (pin "1") (pinfunction "VDD3_0_1") (pintype "power_in"))
    )
    (net (code "27") (name "Net-(IC1-VDD3_1)") (class "Default")
      (node (ref "C22") (pin "1") (pinfunction "1_1") (pintype "passive"))
      (node (ref "C23") (pin "2") (pinfunction "2_2") (pintype "passive"))
      (node (ref "IC1") (pin "32") (pinfunction "VDD3_1_32") (pintype "power_in"))
    )
    (net (code "28") (name "Net-(J1-CC1)") (class "Default")
      (node (ref "J1") (pin "A5") (pinfunction "CC1_A5") (pintype "bidirectional"))
      (node (ref "R1") (pin "2") (pinfunction "2_2") (pintype "passive"))
    )
    (net (code "29") (name "Net-(J1-CC2)") (class "Default")
      (node (ref "J1") (pin "B5") (pinfunction "CC2_B5") (pintype "bidirectional"))
      (node (ref "R2") (pin "1") (pinfunction "1_1") (pintype "passive"))
    )
    (net (code "30") (name "Net-(J1-DN1)") (class "Default")
      (node (ref "C31") (pin "2") (pinfunction "2_2") (pintype "passive"))
      (node (ref "J1") (pin "A7") (pinfunction "DN1_A7") (pintype "bidirectional"))
      (node (ref "J1") (pin "B7") (pinfunction "DN2_B7") (pintype "bidirectional"))
      (node (ref "R9") (pin "1") (pinfunction "1_1") (pintype "passive"))
    )
    (net (code "31") (name "Net-(J1-DP1)") (class "Default")
      (node (ref "C30") (pin "2") (pinfunction "2_2") (pintype "passive"))
      (node (ref "J1") (pin "A6") (pinfunction "DP1_A6") (pintype "bidirectional"))
      (node (ref "J1") (pin "B6") (pinfunction "DP2_B6") (pintype "bidirectional"))
      (node (ref "R8") (pin "1") (pinfunction "1_1") (pintype "passive"))
    )
    (net (code "32") (name "Net-(J1-VBUS-PadA4_B9)") (class "Default")
      (node (ref "J1") (pin "A4_B9") (pinfunction "VBUS_A4_B9") (pintype "power_in"))
      (node (ref "J1") (pin "B4_A9") (pinfunction "VBUS_B4_A9") (pintype "power_in"))
      (node (ref "R7") (pin "2") (pinfunction "2_2") (pintype "passive"))
    )
    (net (code "33") (name "Net-(L1-Pad1)") (class "Default")
      (node (ref "L1") (pin "1") (pinfunction "1_1") (pintype "passive"))
      (node (ref "Q1") (pin "1") (pinfunction "S_1") (pintype "passive"))
      (node (ref "Q1") (pin "2") (pinfunction "S_2") (pintype "passive"))
      (node (ref "Q1") (pin "3") (pinfunction "S_3") (pintype "passive"))
      (node (ref "Q2") (pin "5") (pinfunction "D_5") (pintype "passive"))
      (node (ref "Q2") (pin "6") (pinfunction "D_6") (pintype "passive"))
      (node (ref "Q2") (pin "7") (pinfunction "D_7") (pintype "passive"))
      (node (ref "Q2") (pin "8") (pinfunction "D_8") (pintype "passive"))
      (node (ref "Q2") (pin "9") (pinfunction "D_9") (pintype "passive"))
    )
    (net (code "34") (name "Net-(Q1-G)") (class "Default")
      (node (ref "Q1") (pin "4") (pinfunction "G_4") (pintype "passive"))
      (node (ref "U2") (pin "7") (pinfunction "HDRV_7") (pintype "bidirectional"))
    )
    (net (code "35") (name "Net-(Q2-G)") (class "Default")
      (node (ref "Q2") (pin "4") (pinfunction "G_4") (pintype "passive"))
      (node (ref "R12") (pin "2") (pinfunction "2_2") (pintype "passive"))
      (node (ref "U2") (pin "9") (pinfunction "LDRV_9") (pintype "bidirectional"))
    )
    (net (code "36") (name "Net-(Q3-B)") (class "Default")
      (node (ref "Q3") (pin "1") (pinfunction "B_1") (pintype "passive"))
      (node (ref "R17") (pin "1") (pinfunction "1_1") (pintype "passive"))
      (node (ref "R4") (pin "1") (pinfunction "1_1") (pintype "passive"))
      (node (ref "TP8") (pin "TP") (pinfunction "TP_TP") (pintype "passive"))
      (node (ref "U2") (pin "3") (pinfunction "PGOOD_3") (pintype "bidirectional"))
    )
    (net (code "37") (name "Net-(Q3-C)") (class "Default")
      (node (ref "Q3") (pin "3") (pinfunction "C_3") (pintype "passive"))
      (node (ref "R18") (pin "2") (pinfunction "2_2") (pintype "passive"))
    )
    (net (code "38") (name "Net-(U1-3V3OUT)") (class "Default")
      (node (ref "C3") (pin "1") (pinfunction "1_1") (pintype "passive"))
      (node (ref "TP2") (pin "TP") (pinfunction "TP_TP") (pintype "passive"))
      (node (ref "U1") (pin "10") (pinfunction "3V3OUT_10") (pintype "output"))
    )
    (net (code "39") (name "Net-(U1-CBUS0)") (class "Default")
      (node (ref "R3") (pin "2") (pinfunction "2_2") (pintype "passive"))
      (node (ref "R7") (pin "1") (pinfunction "1_1") (pintype "passive"))
      (node (ref "U1") (pin "15") (pinfunction "CBUS0_15") (pintype "bidirectional"))
    )
    (net (code "40") (name "Net-(U1-CBUS1)") (class "Default")
      (node (ref "R19") (pin "2") (pinfunction "2_2") (pintype "passive"))
      (node (ref "TP1") (pin "TP") (pinfunction "TP_TP") (pintype "passive"))
      (node (ref "U1") (pin "14") (pinfunction "CBUS1_14") (pintype "bidirectional"))
    )
    (net (code "41") (name "Net-(U1-USBDM)") (class "Default")
      (node (ref "R9") (pin "2") (pinfunction "2_2") (pintype "passive"))
      (node (ref "U1") (pin "9") (pinfunction "USBDM_9") (pintype "bidirectional"))
    )
    (net (code "42") (name "Net-(U1-USBDP)") (class "Default")
      (node (ref "R8") (pin "2") (pinfunction "2_2") (pintype "passive"))
      (node (ref "U1") (pin "8") (pinfunction "USBDP_8") (pintype "bidirectional"))
    )
    (net (code "43") (name "Net-(U1-VCC)") (class "Default")
      (node (ref "C1") (pin "1") (pinfunction "1_1") (pintype "passive"))
      (node (ref "C13") (pin "1") (pinfunction "1_1") (pintype "passive"))
      (node (ref "FB1") (pin "2") (pinfunction "2_2") (pintype "passive"))
      (node (ref "U1") (pin "12") (pinfunction "VCC_12") (pintype "power_in"))
    )
    (net (code "44") (name "Net-(U2-BOOT)") (class "Default")
      (node (ref "C6") (pin "2") (pinfunction "2_2") (pintype "passive"))
      (node (ref "U2") (pin "6") (pinfunction "BOOT_6") (pintype "bidirectional"))
    )
    (net (code "45") (name "Net-(U2-BP)") (class "Default")
      (node (ref "C15") (pin "1") (pinfunction "1_1") (pintype "passive"))
      (node (ref "R17") (pin "2") (pinfunction "2_2") (pintype "passive"))
      (node (ref "R6") (pin "1") (pinfunction "1_1") (pintype "passive"))
      (node (ref "U2") (pin "10") (pinfunction "BP_10") (pintype "bidirectional"))
    )
    (net (code "46") (name "Net-(U2-COMP)") (class "Default")
      (node (ref "C40") (pin "1") (pinfunction "1_1") (pintype "passive"))
      (node (ref "C41") (pin "1") (pinfunction "1_1") (pintype "passive"))
      (node (ref "U2") (pin "4") (pinfunction "COMP_4") (pintype "bidirectional"))
    )
    (net (code "47") (name "Net-(U2-FB)") (class "Default")
      (node (ref "C40") (pin "2") (pinfunction "2_2") (pintype "passive"))
      (node (ref "C42") (pin "2") (pinfunction "2_2") (pintype "passive"))
      (node (ref "R10") (pin "1") (pinfunction "1_1") (pintype "passive"))
      (node (ref "R11") (pin "2") (pinfunction "2_2") (pintype "passive"))
      (node (ref "R14") (pin "1") (pinfunction "1_1") (pintype "passive"))
      (node (ref "U2") (pin "5") (pinfunction "FB_5") (pintype "bidirectional"))
    )
    (net (code "48") (name "Net-(U2-SS)") (class "Default")
      (node (ref "C39") (pin "1") (pinfunction "1_1") (pintype "passive"))
      (node (ref "R6") (pin "2") (pinfunction "2_2") (pintype "passive"))
      (node (ref "U2") (pin "2") (pinfunction "SS_2") (pintype "bidirectional"))
    )
    (net (code "49") (name "Net-(U2-SW)") (class "Default")
      (node (ref "C6") (pin "1") (pinfunction "1_1") (pintype "passive"))
      (node (ref "U2") (pin "8") (pinfunction "SW_8") (pintype "bidirectional"))
    )
    (net (code "50") (name "RX") (class "Default")
      (node (ref "IC1") (pin "10") (pinfunction "RO_10") (pintype "output"))
      (node (ref "U1") (pin "1") (pinfunction "RXD_1") (pintype "input"))
    )
    (net (code "51") (name "TX") (class "Default")
      (node (ref "IC1") (pin "11") (pinfunction "CI_11") (pintype "input"))
      (node (ref "U1") (pin "17") (pinfunction "TXD_17") (pintype "output"))
    )
    (net (code "52") (name "unconnected-(BOTFIDUCIAL1-PadTP)") (class "Default")
      (node (ref "BOTFIDUCIAL1") (pin "TP") (pinfunction "TP_TP") (pintype "passive"))
    )
    (net (code "53") (name "unconnected-(IC1-PIN_MODE-Pad20)") (class "Default")
      (node (ref "IC1") (pin "20") (pinfunction "PIN_MODE_20") (pintype "passive"))
    )
    (net (code "54") (name "unconnected-(IC1-RF-Pad23)") (class "Default")
      (node (ref "IC1") (pin "23") (pinfunction "RF_23") (pintype "passive"))
    )
    (net (code "55") (name "unconnected-(IC1-TEST-Pad7)") (class "Default")
      (node (ref "IC1") (pin "7") (pinfunction "TEST_7") (pintype "passive"))
    )
    (net (code "56") (name "unconnected-(IC1-TF-Pad24)") (class "Default")
      (node (ref "IC1") (pin "24") (pinfunction "TF_24") (pintype "passive"))
    )
    (net (code "57") (name "unconnected-(J1-SBU1-PadA8)") (class "Default")
      (node (ref "J1") (pin "A8") (pinfunction "SBU1_A8") (pintype "bidirectional"))
    )
    (net (code "58") (name "unconnected-(J1-SBU2-PadB8)") (class "Default")
      (node (ref "J1") (pin "B8") (pinfunction "SBU2_B8") (pintype "bidirectional"))
    )
    (net (code "59") (name "unconnected-(J2-CC1-PadA5)") (class "Default")
      (node (ref "J2") (pin "A5") (pinfunction "CC1_A5") (pintype "bidirectional"))
    )
    (net (code "60") (name "unconnected-(J2-CC2-PadB5)") (class "Default")
      (node (ref "J2") (pin "B5") (pinfunction "CC2_B5") (pintype "bidirectional"))
    )
    (net (code "61") (name "unconnected-(J2-DN1-PadA7)") (class "Default")
      (node (ref "J2") (pin "A7") (pinfunction "DN1_A7") (pintype "bidirectional"))
    )
    (net (code "62") (name "unconnected-(J2-DN2-PadB7)") (class "Default")
      (node (ref "J2") (pin "B7") (pinfunction "DN2_B7") (pintype "bidirectional"))
    )
    (net (code "63") (name "unconnected-(J2-DP1-PadA6)") (class "Default")
      (node (ref "J2") (pin "A6") (pinfunction "DP1_A6") (pintype "bidirectional"))
    )
    (net (code "64") (name "unconnected-(J2-DP2-PadB6)") (class "Default")
      (node (ref "J2") (pin "B6") (pinfunction "DP2_B6") (pintype "bidirectional"))
    )
    (net (code "65") (name "unconnected-(J2-SBU1-PadA8)") (class "Default")
      (node (ref "J2") (pin "A8") (pinfunction "SBU1_A8") (pintype "bidirectional"))
    )
    (net (code "66") (name "unconnected-(J2-SBU2-PadB8)") (class "Default")
      (node (ref "J2") (pin "B8") (pinfunction "SBU2_B8") (pintype "bidirectional"))
    )
    (net (code "67") (name "unconnected-(J3-CC1-PadA5)") (class "Default")
      (node (ref "J3") (pin "A5") (pinfunction "CC1_A5") (pintype "bidirectional"))
    )
    (net (code "68") (name "unconnected-(J3-CC2-PadB5)") (class "Default")
      (node (ref "J3") (pin "B5") (pinfunction "CC2_B5") (pintype "bidirectional"))
    )
    (net (code "69") (name "unconnected-(J3-DN1-PadA7)") (class "Default")
      (node (ref "J3") (pin "A7") (pinfunction "DN1_A7") (pintype "bidirectional"))
    )
    (net (code "70") (name "unconnected-(J3-DN2-PadB7)") (class "Default")
      (node (ref "J3") (pin "B7") (pinfunction "DN2_B7") (pintype "bidirectional"))
    )
    (net (code "71") (name "unconnected-(J3-DP1-PadA6)") (class "Default")
      (node (ref "J3") (pin "A6") (pinfunction "DP1_A6") (pintype "bidirectional"))
    )
    (net (code "72") (name "unconnected-(J3-DP2-PadB6)") (class "Default")
      (node (ref "J3") (pin "B6") (pinfunction "DP2_B6") (pintype "bidirectional"))
    )
    (net (code "73") (name "unconnected-(J3-SBU1-PadA8)") (class "Default")
      (node (ref "J3") (pin "A8") (pinfunction "SBU1_A8") (pintype "bidirectional"))
    )
    (net (code "74") (name "unconnected-(J3-SBU2-PadB8)") (class "Default")
      (node (ref "J3") (pin "B8") (pinfunction "SBU2_B8") (pintype "bidirectional"))
    )
    (net (code "75") (name "unconnected-(J4-TACH-Pad3)") (class "Default")
      (node (ref "J4") (pin "3") (pinfunction "TACH_3") (pintype "passive"))
    )
    (net (code "76") (name "unconnected-(TOPFIDUCIAL2-PadTP)") (class "Default")
      (node (ref "TOPFIDUCIAL2") (pin "TP") (pinfunction "TP_TP") (pintype "passive"))
    )
    (net (code "77") (name "unconnected-(U1-CTS#-Pad6)") (class "Default")
      (node (ref "U1") (pin "6") (pinfunction "CTS#_6") (pintype "input"))
    )
    (net (code "78") (name "unconnected-(U1-DCD#-Pad5)") (class "Default")
      (node (ref "U1") (pin "5") (pinfunction "DCD#_5") (pintype "input"))
    )
    (net (code "79") (name "unconnected-(U1-DSR#-Pad4)") (class "Default")
      (node (ref "U1") (pin "4") (pinfunction "DSR#_4") (pintype "input"))
    )
    (net (code "80") (name "unconnected-(U1-DTR#-Pad18)") (class "Default")
      (node (ref "U1") (pin "18") (pinfunction "DTR#_18") (pintype "output"))
    )
    (net (code "81") (name "unconnected-(U1-RI#-Pad2)") (class "Default")
      (node (ref "U1") (pin "2") (pinfunction "RI#_2") (pintype "input"))
    )
    (net (code "82") (name "unconnected-(U1-RTS#-Pad19)") (class "Default")
      (node (ref "U1") (pin "19") (pinfunction "RTS#_19") (pintype "output"))
    )
    (net (code "83") (name "~{RST}") (class "Default")
      (node (ref "IC1") (pin "9") (pinfunction "NRSTI_9") (pintype "input"))
      (node (ref "U1") (pin "7") (pinfunction "CBUS2_7") (pintype "bidirectional"))
    )
  )
)
